# Tayloe_Detector_v4.net
KiCad netlist of a schematic drawn in EAGLE
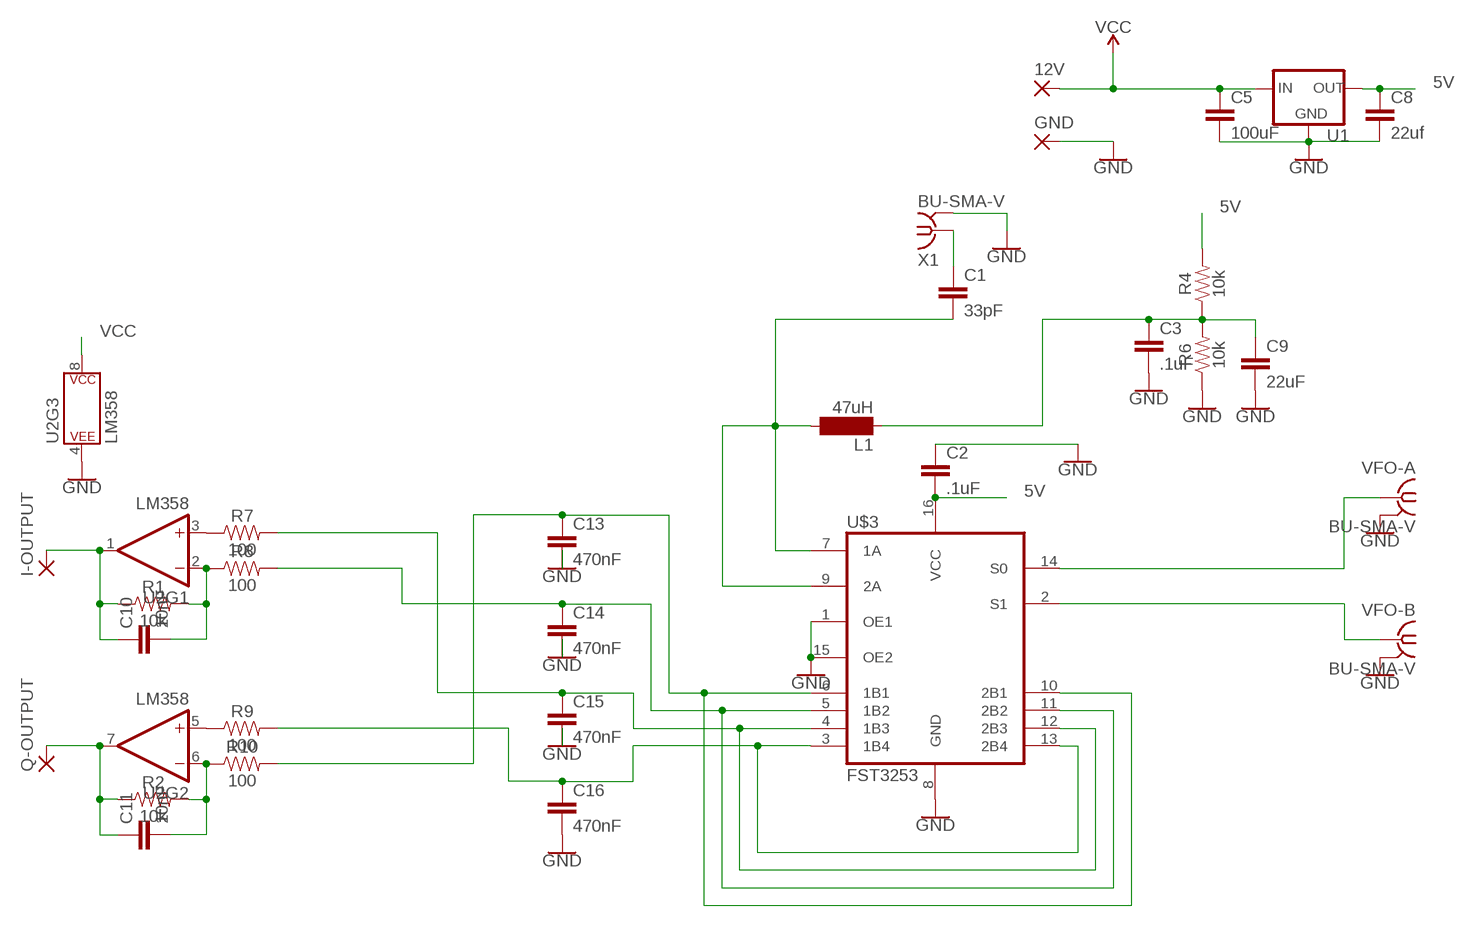
[diagram p0: schematic, sheet 1]

(export (version "E")
  (design (tool "Eeschema 10.0.6"))
  (components
    (comp (ref "12V")
      (value "3,17/1,1")
      (footprint "eagle-import:3,17_1,1")
      (libsource (lib "eagle-import") (part "3,17/1,1"))
    )
    (comp (ref "C1")
      (value "33pF")
      (footprint "eagle-import:C5B3.5")
      (libsource (lib "eagle-import") (part "C5/3.5"))
    )
    (comp (ref "C2")
      (value ".1uF")
      (footprint "eagle-import:C5B3.5")
      (libsource (lib "eagle-import") (part "C5/3.5"))
    )
    (comp (ref "C3")
      (value ".1uF")
      (footprint "eagle-import:C5B3.5")
      (libsource (lib "eagle-import") (part "C5/3.5"))
    )
    (comp (ref "C5")
      (value "100uF")
      (footprint "eagle-import:C5B3.5")
      (libsource (lib "eagle-import") (part "C5/3.5"))
    )
    (comp (ref "C8")
      (value "22uf")
      (footprint "eagle-import:C5B3.5")
      (libsource (lib "eagle-import") (part "C5/3.5"))
    )
    (comp (ref "C9")
      (value "22uF")
      (footprint "eagle-import:C5B3.5")
      (libsource (lib "eagle-import") (part "C5/3.5"))
    )
    (comp (ref "C10")
      (value "10nF")
      (footprint "eagle-import:C5B3.5")
      (libsource (lib "eagle-import") (part "C5/3.5"))
    )
    (comp (ref "C11")
      (value "10nF")
      (footprint "eagle-import:C5B3.5")
      (libsource (lib "eagle-import") (part "C5/3.5"))
    )
    (comp (ref "C13")
      (value "470nF")
      (footprint "eagle-import:C5B3.5")
      (libsource (lib "eagle-import") (part "C5/3.5"))
    )
    (comp (ref "C14")
      (value "470nF")
      (footprint "eagle-import:C5B3.5")
      (libsource (lib "eagle-import") (part "C5/3.5"))
    )
    (comp (ref "C15")
      (value "470nF")
      (footprint "eagle-import:C5B3.5")
      (libsource (lib "eagle-import") (part "C5/3.5"))
    )
    (comp (ref "C16")
      (value "470nF")
      (footprint "eagle-import:C5B3.5")
      (libsource (lib "eagle-import") (part "C5/3.5"))
    )
    (comp (ref "GND")
      (value "3,17/1,1")
      (footprint "eagle-import:3,17_1,1")
      (libsource (lib "eagle-import") (part "3,17/1,1"))
    )
    (comp (ref "I-OUTPUT")
      (value "3,17/1,1")
      (footprint "eagle-import:3,17_1,1")
      (libsource (lib "eagle-import") (part "3,17/1,1"))
    )
    (comp (ref "L1")
      (value "47uH")
      (footprint "eagle-import:BS75")
      (libsource (lib "eagle-import") (part "BS75"))
    )
    (comp (ref "Q-OUTPUT")
      (value "3,17/1,1")
      (footprint "eagle-import:3,17_1,1")
      (libsource (lib "eagle-import") (part "3,17/1,1"))
    )
    (comp (ref "R1")
      (value "10k")
      (footprint "eagle-import:AXIAL-0.3")
      (libsource (lib "eagle-import") (part "1KOHM-HORIZ-1/4W-1%"))
    )
    (comp (ref "R2")
      (value "10k")
      (footprint "eagle-import:AXIAL-0.3")
      (libsource (lib "eagle-import") (part "1KOHM-HORIZ-1/4W-1%"))
    )
    (comp (ref "R4")
      (value "10k")
      (footprint "eagle-import:AXIAL-0.3")
      (libsource (lib "eagle-import") (part "1KOHM-HORIZ-1/4W-1%"))
    )
    (comp (ref "R6")
      (value "10k")
      (footprint "eagle-import:AXIAL-0.3")
      (libsource (lib "eagle-import") (part "1KOHM-HORIZ-1/4W-1%"))
    )
    (comp (ref "R7")
      (value "100")
      (footprint "eagle-import:AXIAL-0.3")
      (libsource (lib "eagle-import") (part "1KOHM-HORIZ-1/4W-1%"))
    )
    (comp (ref "R8")
      (value "100")
      (footprint "eagle-import:AXIAL-0.3")
      (libsource (lib "eagle-import") (part "1KOHM-HORIZ-1/4W-1%"))
    )
    (comp (ref "R9")
      (value "100")
      (footprint "eagle-import:AXIAL-0.3")
      (libsource (lib "eagle-import") (part "1KOHM-HORIZ-1/4W-1%"))
    )
    (comp (ref "R10")
      (value "100")
      (footprint "eagle-import:AXIAL-0.3")
      (libsource (lib "eagle-import") (part "1KOHM-HORIZ-1/4W-1%"))
    )
    (comp (ref "U$3")
      (value "FST3253")
      (footprint "eagle-import:SO16")
      (libsource (lib "eagle-import") (part "FST3253"))
    )
    (comp (ref "U1")
      (value "V_REG_78XXTO-92_UNTESTED")
      (footprint "eagle-import:TO-92")
      (libsource (lib "eagle-import") (part "V_REG_78XXTO-92_UNTESTED"))
    )
    (comp (ref "U2")
      (value "LM358")
      (footprint "eagle-import:DIP08")
      (libsource (lib "eagle-import") (part "LM358"))
    )
    (comp (ref "VFO-A")
      (value "BU-SMA-V")
      (footprint "eagle-import:BU-SMA-V")
      (libsource (lib "eagle-import") (part "BU-SMA-V"))
    )
    (comp (ref "VFO-B")
      (value "BU-SMA-V")
      (footprint "eagle-import:BU-SMA-V")
      (libsource (lib "eagle-import") (part "BU-SMA-V"))
    )
    (comp (ref "X1")
      (value "BU-SMA-V")
      (footprint "eagle-import:BU-SMA-V")
      (libsource (lib "eagle-import") (part "BU-SMA-V"))
    )
  )
  (nets
    (net (code "1") (name "/5V") (class "Default")
      (node (ref "C2") (pin "2") (pinfunction "2_2") (pintype "passive"))
      (node (ref "C8") (pin "1") (pinfunction "1_1") (pintype "passive"))
      (node (ref "R4") (pin "P$2") (pinfunction "2_P$2") (pintype "passive"))
      (node (ref "U$3") (pin "16") (pinfunction "VCC_16") (pintype "bidirectional"))
      (node (ref "U1") (pin "1") (pinfunction "OUT_1") (pintype "passive"))
    )
    (net (code "2") (name "GND") (class "Default")
      (node (ref "C13") (pin "2") (pinfunction "2_2") (pintype "passive"))
      (node (ref "C14") (pin "2") (pinfunction "2_2") (pintype "passive"))
      (node (ref "C15") (pin "2") (pinfunction "2_2") (pintype "passive"))
      (node (ref "C16") (pin "2") (pinfunction "2_2") (pintype "passive"))
      (node (ref "C2") (pin "1") (pinfunction "1_1") (pintype "passive"))
      (node (ref "C3") (pin "2") (pinfunction "2_2") (pintype "passive"))
      (node (ref "C5") (pin "2") (pinfunction "2_2") (pintype "passive"))
      (node (ref "C8") (pin "2") (pinfunction "2_2") (pintype "passive"))
      (node (ref "C9") (pin "2") (pinfunction "2_2") (pintype "passive"))
      (node (ref "GND") (pin "1") (pinfunction "P_1") (pintype "passive"))
      (node (ref "R6") (pin "P$1") (pinfunction "1_P$1") (pintype "passive"))
      (node (ref "U$3") (pin "1") (pinfunction "OE1_1") (pintype "bidirectional"))
      (node (ref "U$3") (pin "15") (pinfunction "OE2_15") (pintype "bidirectional"))
      (node (ref "U$3") (pin "8") (pinfunction "GND_8") (pintype "bidirectional"))
      (node (ref "U1") (pin "2") (pinfunction "GND_2") (pintype "input"))
      (node (ref "U2") (pin "4") (pinfunction "P$V-_4") (pintype "bidirectional"))
      (node (ref "VFO-A") (pin "2") (pinfunction "2_2") (pintype "passive"))
      (node (ref "VFO-A") (pin "3") (pinfunction "2_3") (pintype "passive"))
      (node (ref "VFO-A") (pin "4") (pinfunction "2_4") (pintype "passive"))
      (node (ref "VFO-A") (pin "5") (pinfunction "2_5") (pintype "passive"))
      (node (ref "VFO-B") (pin "2") (pinfunction "2_2") (pintype "passive"))
      (node (ref "VFO-B") (pin "3") (pinfunction "2_3") (pintype "passive"))
      (node (ref "VFO-B") (pin "4") (pinfunction "2_4") (pintype "passive"))
      (node (ref "VFO-B") (pin "5") (pinfunction "2_5") (pintype "passive"))
      (node (ref "X1") (pin "2") (pinfunction "2_2") (pintype "passive"))
      (node (ref "X1") (pin "3") (pinfunction "2_3") (pintype "passive"))
      (node (ref "X1") (pin "4") (pinfunction "2_4") (pintype "passive"))
      (node (ref "X1") (pin "5") (pinfunction "2_5") (pintype "passive"))
    )
    (net (code "3") (name "Net-(C1-Pad1)") (class "Default")
      (node (ref "C1") (pin "1") (pinfunction "1_1") (pintype "passive"))
      (node (ref "X1") (pin "1") (pinfunction "1_1") (pintype "passive"))
    )
    (net (code "4") (name "Net-(I-OUTPUT-P)") (class "Default")
      (node (ref "C10") (pin "1") (pinfunction "1_1") (pintype "passive"))
      (node (ref "I-OUTPUT") (pin "1") (pinfunction "P_1") (pintype "passive"))
      (node (ref "R1") (pin "P$1") (pinfunction "1_P$1") (pintype "passive"))
      (node (ref "U2") (pin "1") (pinfunction "OUT_1") (pintype "output"))
    )
    (net (code "5") (name "Net-(Q-OUTPUT-P)") (class "Default")
      (node (ref "C11") (pin "1") (pinfunction "1_1") (pintype "passive"))
      (node (ref "Q-OUTPUT") (pin "1") (pinfunction "P_1") (pintype "passive"))
      (node (ref "R2") (pin "P$1") (pinfunction "1_P$1") (pintype "passive"))
      (node (ref "U2") (pin "7") (pinfunction "OUT_7") (pintype "output"))
    )
    (net (code "6") (name "Net-(R1-2)") (class "Default")
      (node (ref "C10") (pin "2") (pinfunction "2_2") (pintype "passive"))
      (node (ref "R1") (pin "P$2") (pinfunction "2_P$2") (pintype "passive"))
      (node (ref "R8") (pin "P$1") (pinfunction "1_P$1") (pintype "passive"))
      (node (ref "U2") (pin "2") (pinfunction "-IN_2") (pintype "input"))
    )
    (net (code "7") (name "Net-(R4-1)") (class "Default")
      (node (ref "C3") (pin "1") (pinfunction "1_1") (pintype "passive"))
      (node (ref "C9") (pin "1") (pinfunction "1_1") (pintype "passive"))
      (node (ref "L1") (pin "1") (pinfunction "1_1") (pintype "passive"))
      (node (ref "R4") (pin "P$1") (pinfunction "1_P$1") (pintype "passive"))
      (node (ref "R6") (pin "P$2") (pinfunction "2_P$2") (pintype "passive"))
    )
    (net (code "8") (name "Net-(R7-1)") (class "Default")
      (node (ref "R7") (pin "P$1") (pinfunction "1_P$1") (pintype "passive"))
      (node (ref "U2") (pin "3") (pinfunction "+IN_3") (pintype "input"))
    )
    (net (code "9") (name "Net-(R7-2)") (class "Default")
      (node (ref "C15") (pin "1") (pinfunction "1_1") (pintype "passive"))
      (node (ref "R7") (pin "P$2") (pinfunction "2_P$2") (pintype "passive"))
      (node (ref "U$3") (pin "12") (pinfunction "2B3_12") (pintype "input"))
      (node (ref "U$3") (pin "4") (pinfunction "1B3_4") (pintype "output"))
    )
    (net (code "10") (name "Net-(R8-2)") (class "Default")
      (node (ref "C14") (pin "1") (pinfunction "1_1") (pintype "passive"))
      (node (ref "R8") (pin "P$2") (pinfunction "2_P$2") (pintype "passive"))
      (node (ref "U$3") (pin "11") (pinfunction "2B2_11") (pintype "output"))
      (node (ref "U$3") (pin "5") (pinfunction "1B2_5") (pintype "input"))
    )
    (net (code "11") (name "Net-(R9-1)") (class "Default")
      (node (ref "R9") (pin "P$1") (pinfunction "1_P$1") (pintype "passive"))
      (node (ref "U2") (pin "5") (pinfunction "+IN_5") (pintype "input"))
    )
    (net (code "12") (name "Net-(R9-2)") (class "Default")
      (node (ref "C16") (pin "1") (pinfunction "1_1") (pintype "passive"))
      (node (ref "R9") (pin "P$2") (pinfunction "2_P$2") (pintype "passive"))
      (node (ref "U$3") (pin "13") (pinfunction "2B4_13") (pintype "input"))
      (node (ref "U$3") (pin "3") (pinfunction "1B4_3") (pintype "output"))
    )
    (net (code "13") (name "Net-(R10-1)") (class "Default")
      (node (ref "C11") (pin "2") (pinfunction "2_2") (pintype "passive"))
      (node (ref "R10") (pin "P$1") (pinfunction "1_P$1") (pintype "passive"))
      (node (ref "R2") (pin "P$2") (pinfunction "2_P$2") (pintype "passive"))
      (node (ref "U2") (pin "6") (pinfunction "-IN_6") (pintype "input"))
    )
    (net (code "14") (name "Net-(R10-2)") (class "Default")
      (node (ref "C13") (pin "1") (pinfunction "1_1") (pintype "passive"))
      (node (ref "R10") (pin "P$2") (pinfunction "2_P$2") (pintype "passive"))
      (node (ref "U$3") (pin "10") (pinfunction "2B1_10") (pintype "output"))
      (node (ref "U$3") (pin "6") (pinfunction "1B1_6") (pintype "input"))
    )
    (net (code "15") (name "Net-(U$3-1A)") (class "Default")
      (node (ref "C1") (pin "2") (pinfunction "2_2") (pintype "passive"))
      (node (ref "L1") (pin "2") (pinfunction "2_2") (pintype "passive"))
      (node (ref "U$3") (pin "7") (pinfunction "1A_7") (pintype "bidirectional"))
      (node (ref "U$3") (pin "9") (pinfunction "2A_9") (pintype "bidirectional"))
    )
    (net (code "16") (name "Net-(U$3-S0)") (class "Default")
      (node (ref "U$3") (pin "14") (pinfunction "S0_14") (pintype "bidirectional"))
      (node (ref "VFO-A") (pin "1") (pinfunction "1_1") (pintype "passive"))
    )
    (net (code "17") (name "Net-(U$3-S1)") (class "Default")
      (node (ref "U$3") (pin "2") (pinfunction "S1_2") (pintype "bidirectional"))
      (node (ref "VFO-B") (pin "1") (pinfunction "1_1") (pintype "passive"))
    )
    (net (code "18") (name "VCC") (class "Default")
      (node (ref "12V") (pin "1") (pinfunction "P_1") (pintype "passive"))
      (node (ref "C5") (pin "1") (pinfunction "1_1") (pintype "passive"))
      (node (ref "U1") (pin "3") (pinfunction "IN_3") (pintype "input"))
      (node (ref "U2") (pin "8") (pinfunction "P$V+_8") (pintype "bidirectional"))
    )
  )
)
